# button_ban_dao_schematic.net
KiCad netlist of a schematic drawn in Altium Designer
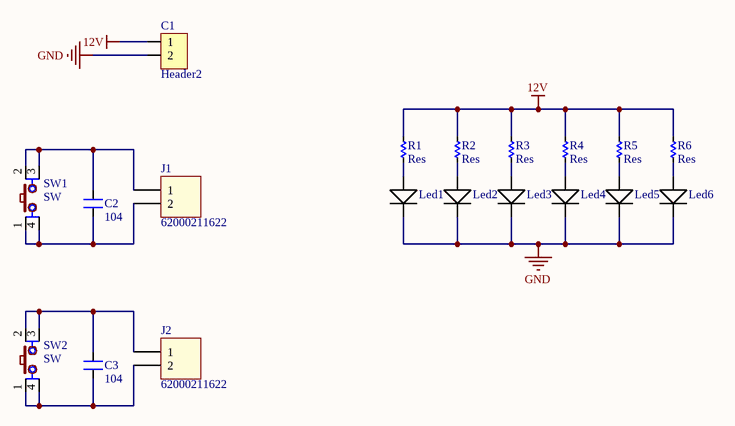
[diagram p0: button_ban_dao_schematic.SchDoc]

(export (version "E")
  (design (tool "Eeschema 10.0.6"))
  (components
    (comp (ref "C1")
      (value "Header2")
      (footprint "Header2")
      (description "Header IDC, 2 x 1 Pin Vertical 2.54mm Pitch (Non-Boxed, Male)")
      (fields
        (field (name "MANUFACTURER") "Würth Elektronik eiSos GmbH")
        (field (name "PARTNO") "613002143121")
        (field (name "CREATED BY") "Karrer Zheng")
      )
      (libsource (lib "LIBRARY") (part "Header2"))
    )
    (comp (ref "C2")
      (value "104")
      (footprint "SM-CAP-0805")
      (fields (field (name "DESIGNED BY") "VanDungEvn"))
      (libsource (lib "electronicvn-library1") (part "CN"))
    )
    (comp (ref "C3")
      (value "104")
      (footprint "SM-CAP-0805")
      (fields (field (name "DESIGNED BY") "VanDungEvn"))
      (libsource (lib "electronicvn-library1") (part "CN"))
    )
    (comp (ref "J1")
      (value "62000211622")
      (footprint "62000211622")
      (description "WR-WTB 2.00mm Male Vertical Shrouded Header, 2p")
      (fields (field (name "PUBLISHER") "Wurth Elektronik"))
      (libsource (lib "Header2.0") (part "62000211622"))
    )
    (comp (ref "J2")
      (value "62000211622")
      (footprint "62000211622")
      (description "WR-WTB 2.00mm Male Vertical Shrouded Header, 2p")
      (fields (field (name "PUBLISHER") "Wurth Elektronik"))
      (libsource (lib "Header2.0") (part "62000211622"))
    )
    (comp (ref "Led1") (value "LED5730") (footprint "LED5730") (libsource (lib "LED5730") (part "LED5730")))
    (comp (ref "Led2") (value "LED5730") (footprint "LED5730") (libsource (lib "LED5730") (part "LED5730")))
    (comp (ref "Led3") (value "LED5730") (footprint "LED5730") (libsource (lib "LED5730") (part "LED5730")))
    (comp (ref "Led4") (value "LED5730") (footprint "LED5730") (libsource (lib "LED5730") (part "LED5730")))
    (comp (ref "Led5") (value "LED5730") (footprint "LED5730") (libsource (lib "LED5730") (part "LED5730")))
    (comp (ref "Led6") (value "LED5730") (footprint "LED5730") (libsource (lib "LED5730") (part "LED5730")))
    (comp (ref "R1")
      (value "Res")
      (footprint "RES-SMD-0805")
      (description "Resistor")
      (fields
        (field (name "MANUFACTURER") "Generic Components")
        (field (name "PUBLISHER") "Altium Hobart Technology Centre")
      )
      (libsource (lib "LIBRARY") (part "Res-SMD"))
    )
    (comp (ref "R2")
      (value "Res")
      (footprint "RES-SMD-0805")
      (description "Resistor")
      (fields
        (field (name "MANUFACTURER") "Generic Components")
        (field (name "PUBLISHER") "Altium Hobart Technology Centre")
      )
      (libsource (lib "LIBRARY") (part "Res-SMD"))
    )
    (comp (ref "R3")
      (value "Res")
      (footprint "RES-SMD-0805")
      (description "Resistor")
      (fields
        (field (name "MANUFACTURER") "Generic Components")
        (field (name "PUBLISHER") "Altium Hobart Technology Centre")
      )
      (libsource (lib "LIBRARY") (part "Res-SMD"))
    )
    (comp (ref "R4")
      (value "Res")
      (footprint "RES-SMD-0805")
      (description "Resistor")
      (fields
        (field (name "MANUFACTURER") "Generic Components")
        (field (name "PUBLISHER") "Altium Hobart Technology Centre")
      )
      (libsource (lib "LIBRARY") (part "Res-SMD"))
    )
    (comp (ref "R5")
      (value "Res")
      (footprint "RES-SMD-0805")
      (description "Resistor")
      (fields
        (field (name "MANUFACTURER") "Generic Components")
        (field (name "PUBLISHER") "Altium Hobart Technology Centre")
      )
      (libsource (lib "LIBRARY") (part "Res-SMD"))
    )
    (comp (ref "R6")
      (value "Res")
      (footprint "RES-SMD-0805")
      (description "Resistor")
      (fields
        (field (name "MANUFACTURER") "Generic Components")
        (field (name "PUBLISHER") "Altium Hobart Technology Centre")
      )
      (libsource (lib "LIBRARY") (part "Res-SMD"))
    )
    (comp (ref "SW1")
      (value "SW")
      (footprint "SW2-SMD")
      (description "Switch button 4 pin")
      (libsource (lib "LIBRARY") (part "SW4"))
    )
    (comp (ref "SW2")
      (value "SW")
      (footprint "SW2-SMD")
      (description "Switch button 4 pin")
      (libsource (lib "LIBRARY") (part "SW4"))
    )
  )
  (nets
    (net (code "1") (name "12V") (class "Default")
      (node (ref "C1") (pin "1") (pinfunction "1_1") (pintype "passive"))
      (node (ref "R1") (pin "1") (pinfunction "1_1") (pintype "passive"))
      (node (ref "R2") (pin "1") (pinfunction "1_1") (pintype "passive"))
      (node (ref "R3") (pin "1") (pinfunction "1_1") (pintype "passive"))
      (node (ref "R4") (pin "1") (pinfunction "1_1") (pintype "passive"))
      (node (ref "R5") (pin "1") (pinfunction "1_1") (pintype "passive"))
      (node (ref "R6") (pin "1") (pinfunction "1_1") (pintype "passive"))
    )
    (net (code "2") (name "GND") (class "Default")
      (node (ref "C1") (pin "2") (pinfunction "2_2") (pintype "passive"))
      (node (ref "Led1") (pin "1") (pinfunction "1_1") (pintype "passive"))
      (node (ref "Led2") (pin "1") (pinfunction "1_1") (pintype "passive"))
      (node (ref "Led3") (pin "1") (pinfunction "1_1") (pintype "passive"))
      (node (ref "Led4") (pin "1") (pinfunction "1_1") (pintype "passive"))
      (node (ref "Led5") (pin "1") (pinfunction "1_1") (pintype "passive"))
      (node (ref "Led6") (pin "1") (pinfunction "1_1") (pintype "passive"))
    )
    (net (code "3") (name "Net-(C2-Pad1)") (class "Default")
      (node (ref "C2") (pin "1") (pinfunction "1_1") (pintype "passive"))
      (node (ref "J1") (pin "2") (pinfunction "2_2") (pintype "passive"))
      (node (ref "SW1") (pin "1") (pintype "passive"))
      (node (ref "SW1") (pin "4") (pinfunction "4_4") (pintype "passive"))
    )
    (net (code "4") (name "Net-(C2-Pad2)") (class "Default")
      (node (ref "C2") (pin "2") (pinfunction "2_2") (pintype "passive"))
      (node (ref "J1") (pin "1") (pinfunction "1_1") (pintype "passive"))
      (node (ref "SW1") (pin "2") (pinfunction "2_2") (pintype "passive"))
      (node (ref "SW1") (pin "3") (pinfunction "3_3") (pintype "passive"))
    )
    (net (code "5") (name "Net-(C3-Pad1)") (class "Default")
      (node (ref "C3") (pin "1") (pinfunction "1_1") (pintype "passive"))
      (node (ref "J2") (pin "2") (pinfunction "2_2") (pintype "passive"))
      (node (ref "SW2") (pin "1") (pintype "passive"))
      (node (ref "SW2") (pin "4") (pinfunction "4_4") (pintype "passive"))
    )
    (net (code "6") (name "Net-(C3-Pad2)") (class "Default")
      (node (ref "C3") (pin "2") (pinfunction "2_2") (pintype "passive"))
      (node (ref "J2") (pin "1") (pinfunction "1_1") (pintype "passive"))
      (node (ref "SW2") (pin "2") (pinfunction "2_2") (pintype "passive"))
      (node (ref "SW2") (pin "3") (pinfunction "3_3") (pintype "passive"))
    )
    (net (code "7") (name "Net-(Led1-Pad0)") (class "Default")
      (node (ref "Led1") (pin "0") (pinfunction "0_0") (pintype "passive"))
      (node (ref "R1") (pin "2") (pinfunction "2_2") (pintype "passive"))
    )
    (net (code "8") (name "Net-(Led2-Pad0)") (class "Default")
      (node (ref "Led2") (pin "0") (pinfunction "0_0") (pintype "passive"))
      (node (ref "R2") (pin "2") (pinfunction "2_2") (pintype "passive"))
    )
    (net (code "9") (name "Net-(Led3-Pad0)") (class "Default")
      (node (ref "Led3") (pin "0") (pinfunction "0_0") (pintype "passive"))
      (node (ref "R3") (pin "2") (pinfunction "2_2") (pintype "passive"))
    )
    (net (code "10") (name "Net-(Led4-Pad0)") (class "Default")
      (node (ref "Led4") (pin "0") (pinfunction "0_0") (pintype "passive"))
      (node (ref "R4") (pin "2") (pinfunction "2_2") (pintype "passive"))
    )
    (net (code "11") (name "Net-(Led5-Pad0)") (class "Default")
      (node (ref "Led5") (pin "0") (pinfunction "0_0") (pintype "passive"))
      (node (ref "R5") (pin "2") (pinfunction "2_2") (pintype "passive"))
    )
    (net (code "12") (name "Net-(Led6-Pad0)") (class "Default")
      (node (ref "Led6") (pin "0") (pinfunction "0_0") (pintype "passive"))
      (node (ref "R6") (pin "2") (pinfunction "2_2") (pintype "passive"))
    )
  )
)
